# AJH_as3340_20.net
KiCad netlist of a schematic drawn in EAGLE
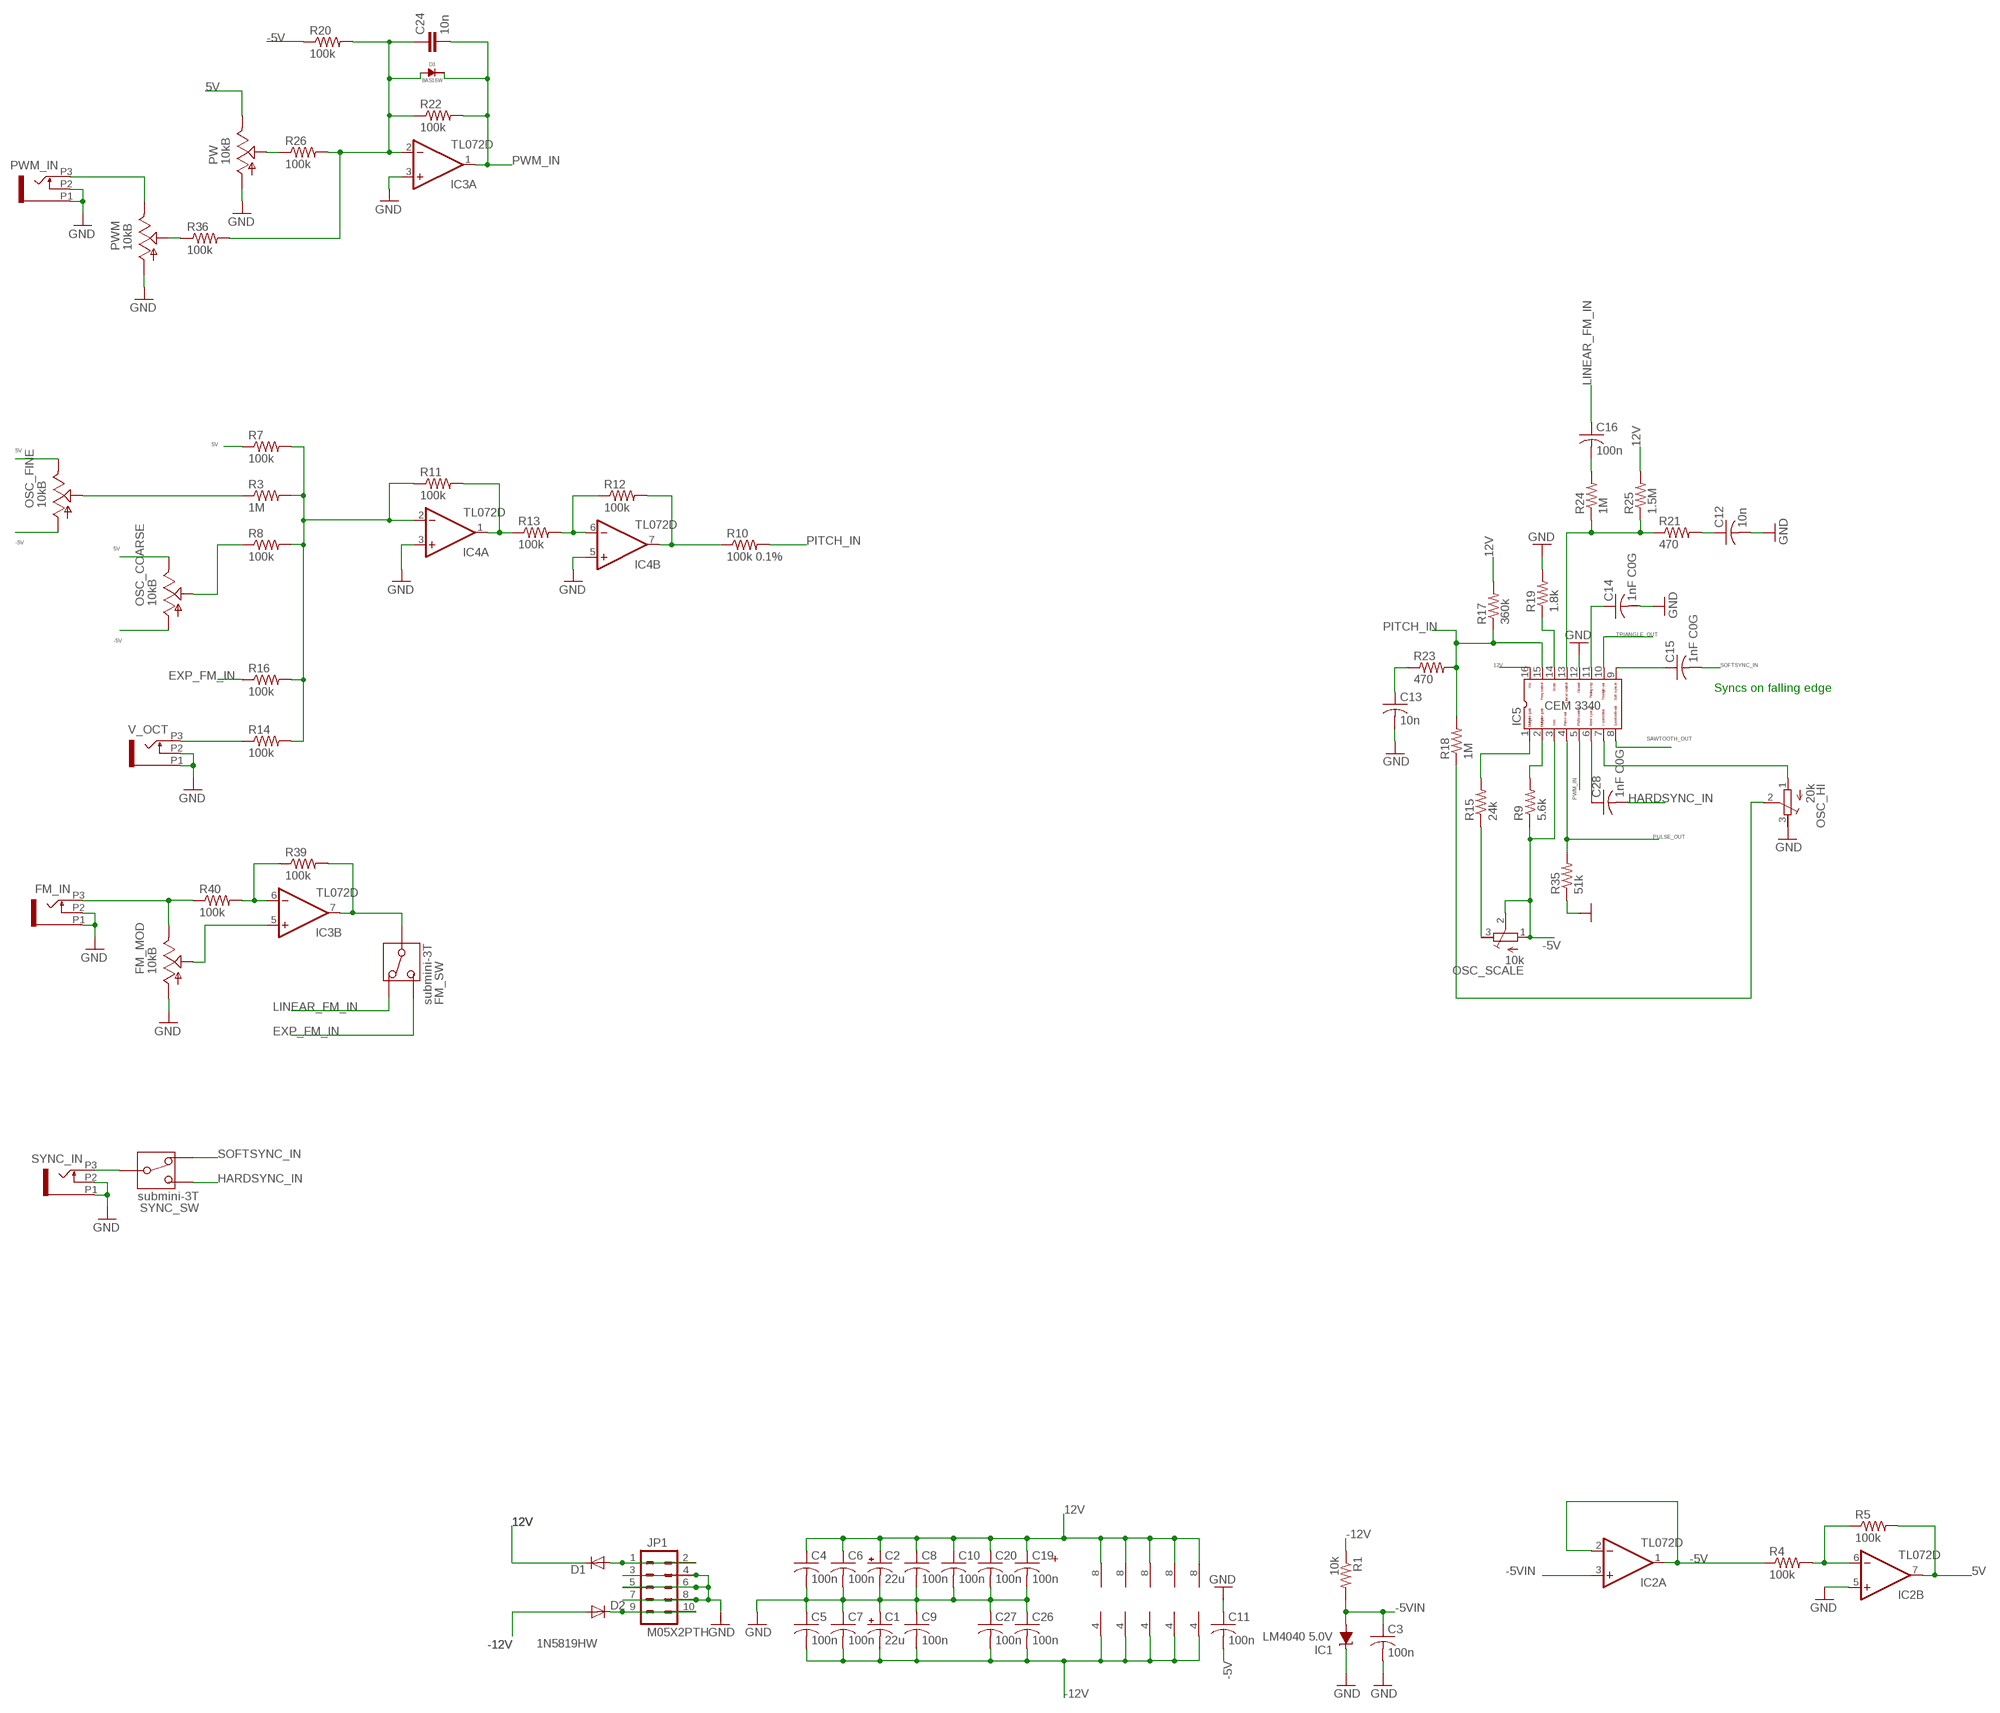
[diagram p0: schematic, sheet 1, part 1 of 2]
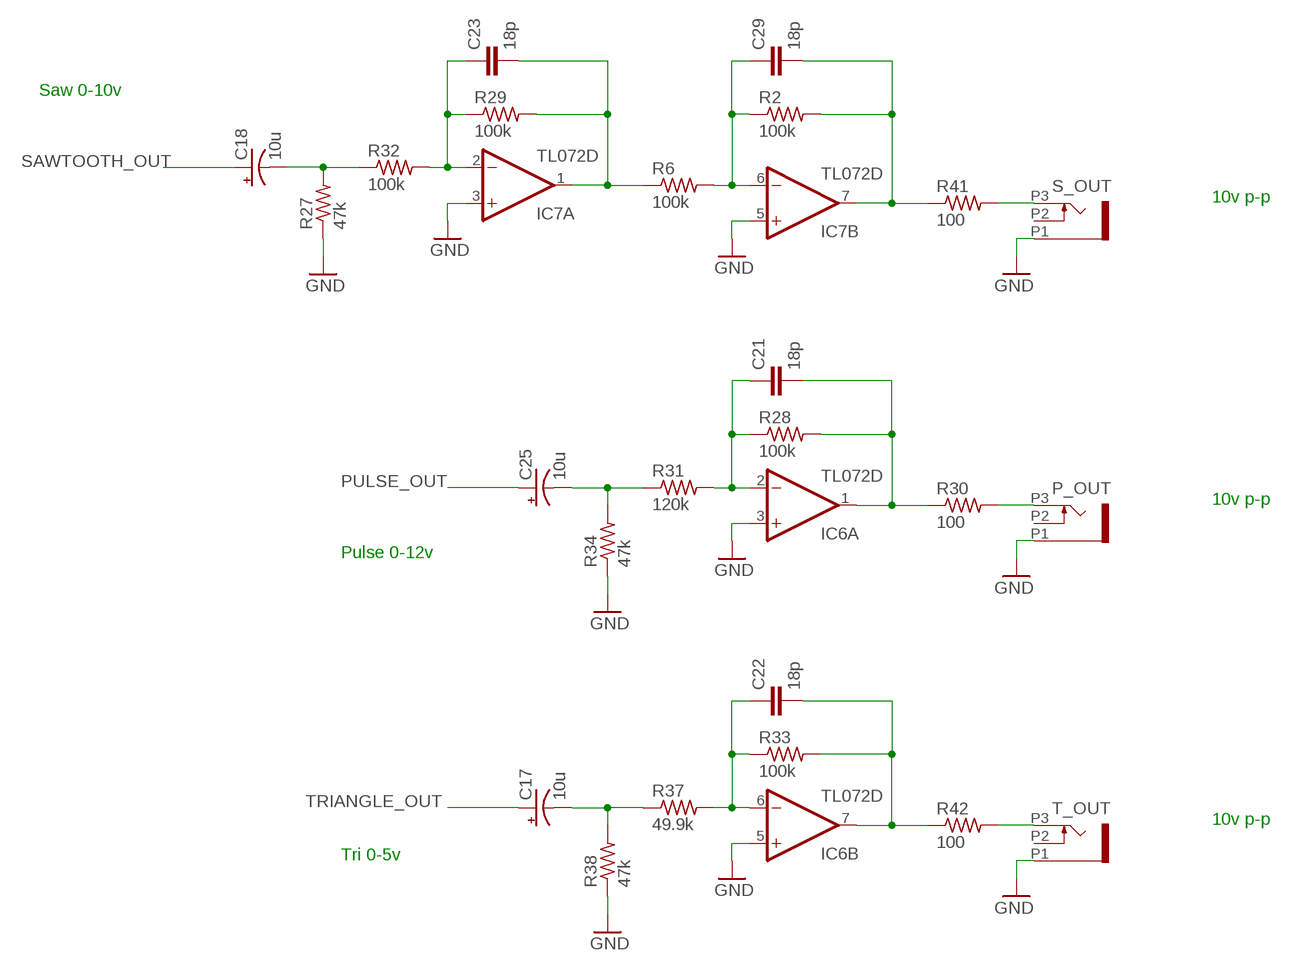
[diagram p1: schematic, sheet 1, part 2 of 2]

(export (version "E")
  (design (tool "Eeschema 10.0.6"))
  (components
    (comp (ref "C1")
      (value "22u")
      (footprint "eagle-import:PANASONIC_B")
      (libsource (lib "eagle-import") (part "CPOL-USB"))
    )
    (comp (ref "C2")
      (value "22u")
      (footprint "eagle-import:PANASONIC_B")
      (libsource (lib "eagle-import") (part "CPOL-USB"))
    )
    (comp (ref "C3")
      (value "100n")
      (footprint "eagle-import:C0603")
      (libsource (lib "eagle-import") (part "C-USC0603"))
    )
    (comp (ref "C4")
      (value "100n")
      (footprint "eagle-import:C0603")
      (libsource (lib "eagle-import") (part "C-USC0603"))
    )
    (comp (ref "C5")
      (value "100n")
      (footprint "eagle-import:C0603")
      (libsource (lib "eagle-import") (part "C-USC0603"))
    )
    (comp (ref "C6")
      (value "100n")
      (footprint "eagle-import:C0603")
      (libsource (lib "eagle-import") (part "C-USC0603"))
    )
    (comp (ref "C7")
      (value "100n")
      (footprint "eagle-import:C0603")
      (libsource (lib "eagle-import") (part "C-USC0603"))
    )
    (comp (ref "C8")
      (value "100n")
      (footprint "eagle-import:C0603")
      (libsource (lib "eagle-import") (part "C-USC0603"))
    )
    (comp (ref "C9")
      (value "100n")
      (footprint "eagle-import:C0603")
      (libsource (lib "eagle-import") (part "C-USC0603"))
    )
    (comp (ref "C10")
      (value "100n")
      (footprint "eagle-import:C0603")
      (libsource (lib "eagle-import") (part "C-USC0603"))
    )
    (comp (ref "C11")
      (value "100n")
      (footprint "eagle-import:C0603")
      (libsource (lib "eagle-import") (part "C-USC0603"))
    )
    (comp (ref "C12")
      (value "10n")
      (footprint "eagle-import:C0603")
      (libsource (lib "eagle-import") (part "C-USC0603"))
    )
    (comp (ref "C13")
      (value "10n")
      (footprint "eagle-import:C0603")
      (libsource (lib "eagle-import") (part "C-USC0603"))
    )
    (comp (ref "C14")
      (value "1nF C0G")
      (footprint "eagle-import:C0603")
      (libsource (lib "eagle-import") (part "C-USC0603"))
    )
    (comp (ref "C15")
      (value "1nF C0G")
      (footprint "eagle-import:C0603")
      (libsource (lib "eagle-import") (part "C-USC0603"))
    )
    (comp (ref "C16")
      (value "100n")
      (footprint "eagle-import:C0603")
      (libsource (lib "eagle-import") (part "C-USC0603"))
    )
    (comp (ref "C17")
      (value "10u")
      (footprint "eagle-import:PANASONIC_B")
      (libsource (lib "eagle-import") (part "CPOL-USB"))
    )
    (comp (ref "C18")
      (value "10u")
      (footprint "eagle-import:PANASONIC_B")
      (libsource (lib "eagle-import") (part "CPOL-USB"))
    )
    (comp (ref "C19")
      (value "100n")
      (footprint "eagle-import:C0603")
      (libsource (lib "eagle-import") (part "C-USC0603"))
    )
    (comp (ref "C20")
      (value "100n")
      (footprint "eagle-import:C0603")
      (libsource (lib "eagle-import") (part "C-USC0603"))
    )
    (comp (ref "C21")
      (value "18p")
      (footprint "eagle-import:C0603")
      (libsource (lib "eagle-import") (part "C-EUC0603"))
    )
    (comp (ref "C22")
      (value "18p")
      (footprint "eagle-import:C0603")
      (libsource (lib "eagle-import") (part "C-EUC0603"))
    )
    (comp (ref "C23")
      (value "18p")
      (footprint "eagle-import:C0603")
      (libsource (lib "eagle-import") (part "C-EUC0603"))
    )
    (comp (ref "C24")
      (value "10n")
      (footprint "eagle-import:C0603")
      (libsource (lib "eagle-import") (part "C-EUC0603"))
    )
    (comp (ref "C25")
      (value "10u")
      (footprint "eagle-import:PANASONIC_B")
      (libsource (lib "eagle-import") (part "CPOL-USB"))
    )
    (comp (ref "C26")
      (value "100n")
      (footprint "eagle-import:C0603")
      (libsource (lib "eagle-import") (part "C-USC0603"))
    )
    (comp (ref "C27")
      (value "100n")
      (footprint "eagle-import:C0603")
      (libsource (lib "eagle-import") (part "C-USC0603"))
    )
    (comp (ref "C28")
      (value "1nF C0G")
      (footprint "eagle-import:C0603")
      (libsource (lib "eagle-import") (part "C-USC0603"))
    )
    (comp (ref "C29")
      (value "18p")
      (footprint "eagle-import:C0603")
      (libsource (lib "eagle-import") (part "C-EUC0603"))
    )
    (comp (ref "D1")
      (value "1N5819HW")
      (footprint "eagle-import:SOD123")
      (libsource (lib "eagle-import") (part "DIODE-SOD123"))
    )
    (comp (ref "D2")
      (value "1N5819HW")
      (footprint "eagle-import:SOD123")
      (libsource (lib "eagle-import") (part "DIODE-SOD123"))
    )
    (comp (ref "D3")
      (value "BAS16W")
      (footprint "eagle-import:SOT-323")
      (libsource (lib "eagle-import") (part "BAS16W"))
    )
    (comp (ref "FM_IN")
      (value "PJ301_THONKICONN6")
      (footprint "eagle-import:WQP_PJ_301M6")
      (libsource (lib "eagle-import") (part "PJ301_THONKICONN6"))
    )
    (comp (ref "FM_MOD")
      (value "10kB")
      (footprint "eagle-import:ALPS_POT_VERTICAL_PS")
      (libsource (lib "eagle-import") (part "pot-alps_POT_USVERTICAL_PS"))
    )
    (comp (ref "FM_SW")
      (value "submini-3T")
      (footprint "eagle-import:SPDT-SUB")
      (libsource (lib "eagle-import") (part "SPDTT"))
    )
    (comp (ref "IC1")
      (value "LM4040 5.0V")
      (footprint "eagle-import:DBZ_R-PDSO-G3")
      (libsource (lib "eagle-import") (part "LM4041DBZC12"))
    )
    (comp (ref "IC2")
      (value "TL072D")
      (footprint "eagle-import:SO08")
      (libsource (lib "eagle-import") (part "TL072D"))
    )
    (comp (ref "IC3")
      (value "TL072D")
      (footprint "eagle-import:SO08")
      (libsource (lib "eagle-import") (part "TL072D"))
    )
    (comp (ref "IC4")
      (value "TL072D")
      (footprint "eagle-import:SO08")
      (libsource (lib "eagle-import") (part "TL072D"))
    )
    (comp (ref "IC5")
      (value "CEM3340SOIC16")
      (footprint "eagle-import:SO16")
      (libsource (lib "eagle-import") (part "CEM3340SOIC16"))
    )
    (comp (ref "IC6")
      (value "TL072D")
      (footprint "eagle-import:SO08")
      (libsource (lib "eagle-import") (part "TL072D"))
    )
    (comp (ref "IC7")
      (value "TL072D")
      (footprint "eagle-import:SO08")
      (libsource (lib "eagle-import") (part "TL072D"))
    )
    (comp (ref "JP1")
      (value "M05X2PTH")
      (footprint "eagle-import:AVR_ICSP")
      (libsource (lib "eagle-import") (part "M05X2PTH"))
    )
    (comp (ref "OSC_COARSE")
      (value "10kB")
      (footprint "eagle-import:ALPS_POT_VERTICAL")
      (libsource (lib "eagle-import") (part "POT_USVERTICAL"))
    )
    (comp (ref "OSC_FINE")
      (value "10kB")
      (footprint "eagle-import:ALPS_POT_VERTICAL")
      (libsource (lib "eagle-import") (part "POT_USVERTICAL"))
    )
    (comp (ref "OSC_HI")
      (value "20k")
      (footprint "eagle-import:RTRIM3296X")
      (libsource (lib "eagle-import") (part "R-TRIMM3296X"))
    )
    (comp (ref "OSC_SCALE")
      (value "10k")
      (footprint "eagle-import:RTRIM3296X")
      (libsource (lib "eagle-import") (part "R-TRIMM3296X"))
    )
    (comp (ref "PW")
      (value "10kB")
      (footprint "eagle-import:ALPS_POT_VERTICAL_PS")
      (libsource (lib "eagle-import") (part "pot-alps_POT_USVERTICAL_PS"))
    )
    (comp (ref "PWM")
      (value "10kB")
      (footprint "eagle-import:ALPS_POT_VERTICAL_PS")
      (libsource (lib "eagle-import") (part "pot-alps_POT_USVERTICAL_PS"))
    )
    (comp (ref "PWM_IN")
      (value "PJ301_THONKICONN6")
      (footprint "eagle-import:WQP_PJ_301M6")
      (libsource (lib "eagle-import") (part "PJ301_THONKICONN6"))
    )
    (comp (ref "P_OUT")
      (value "PJ301_THONKICONN6")
      (footprint "eagle-import:WQP_PJ_301M6")
      (libsource (lib "eagle-import") (part "PJ301_THONKICONN6"))
    )
    (comp (ref "R1")
      (value "10k")
      (footprint "eagle-import:R0603")
      (libsource (lib "eagle-import") (part "R-US_R0603"))
    )
    (comp (ref "R2")
      (value "100k")
      (footprint "eagle-import:R0603")
      (libsource (lib "eagle-import") (part "R-US_R0603"))
    )
    (comp (ref "R3")
      (value "1M")
      (footprint "eagle-import:R0603")
      (libsource (lib "eagle-import") (part "R-US_R0603"))
    )
    (comp (ref "R4")
      (value "100k")
      (footprint "eagle-import:R0603")
      (libsource (lib "eagle-import") (part "R-US_R0603"))
    )
    (comp (ref "R5")
      (value "100k")
      (footprint "eagle-import:R0603")
      (libsource (lib "eagle-import") (part "R-US_R0603"))
    )
    (comp (ref "R6")
      (value "100k")
      (footprint "eagle-import:R0603")
      (libsource (lib "eagle-import") (part "R-US_R0603"))
    )
    (comp (ref "R7")
      (value "100k")
      (footprint "eagle-import:R0603")
      (libsource (lib "eagle-import") (part "R-US_R0603"))
    )
    (comp (ref "R8")
      (value "100k")
      (footprint "eagle-import:R0603")
      (libsource (lib "eagle-import") (part "R-US_R0603"))
    )
    (comp (ref "R9")
      (value "5.6k")
      (footprint "eagle-import:R0603")
      (libsource (lib "eagle-import") (part "R-US_R0603"))
    )
    (comp (ref "R10")
      (value "100k 0.1%")
      (footprint "eagle-import:R0603")
      (libsource (lib "eagle-import") (part "R-US_R0603"))
    )
    (comp (ref "R11")
      (value "100k")
      (footprint "eagle-import:R0603")
      (libsource (lib "eagle-import") (part "R-US_R0603"))
    )
    (comp (ref "R12")
      (value "100k")
      (footprint "eagle-import:R0603")
      (libsource (lib "eagle-import") (part "R-US_R0603"))
    )
    (comp (ref "R13")
      (value "100k")
      (footprint "eagle-import:R0603")
      (libsource (lib "eagle-import") (part "R-US_R0603"))
    )
    (comp (ref "R14")
      (value "100k")
      (footprint "eagle-import:R0603")
      (libsource (lib "eagle-import") (part "R-US_R0603"))
    )
    (comp (ref "R15")
      (value "24k")
      (footprint "eagle-import:R0603")
      (libsource (lib "eagle-import") (part "R-US_R0603"))
    )
    (comp (ref "R16")
      (value "100k")
      (footprint "eagle-import:R0603")
      (libsource (lib "eagle-import") (part "R-US_R0603"))
    )
    (comp (ref "R17")
      (value "360k")
      (footprint "eagle-import:R0603")
      (libsource (lib "eagle-import") (part "R-US_R0603"))
    )
    (comp (ref "R18")
      (value "1M")
      (footprint "eagle-import:R0603")
      (libsource (lib "eagle-import") (part "R-US_R0603"))
    )
    (comp (ref "R19")
      (value "1.8k")
      (footprint "eagle-import:R0603")
      (libsource (lib "eagle-import") (part "R-US_R0603"))
    )
    (comp (ref "R20")
      (value "100k")
      (footprint "eagle-import:R0603")
      (libsource (lib "eagle-import") (part "R-US_R0603"))
    )
    (comp (ref "R21")
      (value "470")
      (footprint "eagle-import:R0603")
      (libsource (lib "eagle-import") (part "R-US_R0603"))
    )
    (comp (ref "R22")
      (value "100k")
      (footprint "eagle-import:R0603")
      (libsource (lib "eagle-import") (part "R-US_R0603"))
    )
    (comp (ref "R23")
      (value "470")
      (footprint "eagle-import:R0603")
      (libsource (lib "eagle-import") (part "R-US_R0603"))
    )
    (comp (ref "R24")
      (value "1M")
      (footprint "eagle-import:R0603")
      (libsource (lib "eagle-import") (part "R-US_R0603"))
    )
    (comp (ref "R25")
      (value "1.5M")
      (footprint "eagle-import:R0603")
      (libsource (lib "eagle-import") (part "R-US_R0603"))
    )
    (comp (ref "R26")
      (value "100k")
      (footprint "eagle-import:R0603")
      (libsource (lib "eagle-import") (part "R-US_R0603"))
    )
    (comp (ref "R27")
      (value "47k")
      (footprint "eagle-import:R0603")
      (libsource (lib "eagle-import") (part "R-US_R0603"))
    )
    (comp (ref "R28")
      (value "100k")
      (footprint "eagle-import:R0603")
      (libsource (lib "eagle-import") (part "R-US_R0603"))
    )
    (comp (ref "R29")
      (value "100k")
      (footprint "eagle-import:R0603")
      (libsource (lib "eagle-import") (part "R-US_R0603"))
    )
    (comp (ref "R30")
      (value "100")
      (footprint "eagle-import:R0603")
      (libsource (lib "eagle-import") (part "R-US_R0603"))
    )
    (comp (ref "R31")
      (value "120k")
      (footprint "eagle-import:R0603")
      (libsource (lib "eagle-import") (part "R-US_R0603"))
    )
    (comp (ref "R32")
      (value "100k")
      (footprint "eagle-import:R0603")
      (libsource (lib "eagle-import") (part "R-US_R0603"))
    )
    (comp (ref "R33")
      (value "100k")
      (footprint "eagle-import:R0603")
      (libsource (lib "eagle-import") (part "R-US_R0603"))
    )
    (comp (ref "R34")
      (value "47k")
      (footprint "eagle-import:R0603")
      (libsource (lib "eagle-import") (part "R-US_R0603"))
    )
    (comp (ref "R35")
      (value "51k")
      (footprint "eagle-import:R0603")
      (libsource (lib "eagle-import") (part "R-US_R0603"))
    )
    (comp (ref "R36")
      (value "100k")
      (footprint "eagle-import:R0603")
      (libsource (lib "eagle-import") (part "R-US_R0603"))
    )
    (comp (ref "R37")
      (value "49.9k")
      (footprint "eagle-import:R0603")
      (libsource (lib "eagle-import") (part "R-US_R0603"))
    )
    (comp (ref "R38")
      (value "47k")
      (footprint "eagle-import:R0603")
      (libsource (lib "eagle-import") (part "R-US_R0603"))
    )
    (comp (ref "R39")
      (value "100k")
      (footprint "eagle-import:R0603")
      (libsource (lib "eagle-import") (part "R-US_R0603"))
    )
    (comp (ref "R40")
      (value "100k")
      (footprint "eagle-import:R0603")
      (libsource (lib "eagle-import") (part "R-US_R0603"))
    )
    (comp (ref "R41")
      (value "100")
      (footprint "eagle-import:R0603")
      (libsource (lib "eagle-import") (part "R-US_R0603"))
    )
    (comp (ref "R42")
      (value "100")
      (footprint "eagle-import:R0603")
      (libsource (lib "eagle-import") (part "R-US_R0603"))
    )
    (comp (ref "SYNC_IN")
      (value "PJ301_THONKICONN6")
      (footprint "eagle-import:WQP_PJ_301M6")
      (libsource (lib "eagle-import") (part "PJ301_THONKICONN6"))
    )
    (comp (ref "SYNC_SW")
      (value "submini-3T")
      (footprint "eagle-import:SPDT-SUB")
      (libsource (lib "eagle-import") (part "SPDTT"))
    )
    (comp (ref "S_OUT")
      (value "PJ301_THONKICONN6")
      (footprint "eagle-import:WQP_PJ_301M6")
      (libsource (lib "eagle-import") (part "PJ301_THONKICONN6"))
    )
    (comp (ref "T_OUT")
      (value "PJ301_THONKICONN6")
      (footprint "eagle-import:WQP_PJ_301M6")
      (libsource (lib "eagle-import") (part "PJ301_THONKICONN6"))
    )
    (comp (ref "V_OCT")
      (value "PJ301_THONKICONN6")
      (footprint "eagle-import:WQP_PJ_301M6")
      (libsource (lib "eagle-import") (part "PJ301_THONKICONN6"))
    )
  )
  (nets
    (net (code "1") (name "/-5V") (class "Default")
      (node (ref "C11") (pin "2") (pinfunction "2_2") (pintype "passive"))
      (node (ref "IC2") (pin "1") (pinfunction "OUT_1") (pintype "output"))
      (node (ref "IC2") (pin "2") (pinfunction "-IN_2") (pintype "input"))
      (node (ref "IC5") (pin "3") (pinfunction "3_3") (pintype "power_in"))
      (node (ref "OSC_COARSE") (pin "P$3") (pinfunction "A_P$3") (pintype "passive"))
      (node (ref "OSC_FINE") (pin "P$3") (pinfunction "A_P$3") (pintype "passive"))
      (node (ref "OSC_SCALE") (pin "1") (pinfunction "E_1") (pintype "passive"))
      (node (ref "OSC_SCALE") (pin "2") (pinfunction "S_2") (pintype "passive"))
      (node (ref "R20") (pin "1") (pinfunction "1_1") (pintype "passive"))
      (node (ref "R4") (pin "1") (pinfunction "1_1") (pintype "passive"))
      (node (ref "R9") (pin "1") (pinfunction "1_1") (pintype "passive"))
    )
    (net (code "2") (name "/-5VIN") (class "Default")
      (node (ref "C3") (pin "1") (pinfunction "1_1") (pintype "passive"))
      (node (ref "IC1") (pin "2") (pinfunction "A_2") (pintype "passive"))
      (node (ref "IC2") (pin "3") (pinfunction "+IN_3") (pintype "input"))
      (node (ref "R1") (pin "2") (pinfunction "2_2") (pintype "passive"))
    )
    (net (code "3") (name "/-12V") (class "Default")
      (node (ref "C1") (pin "-") (pinfunction "-_-") (pintype "passive"))
      (node (ref "C26") (pin "2") (pinfunction "2_2") (pintype "passive"))
      (node (ref "C27") (pin "2") (pinfunction "2_2") (pintype "passive"))
      (node (ref "C5") (pin "2") (pinfunction "2_2") (pintype "passive"))
      (node (ref "C7") (pin "2") (pinfunction "2_2") (pintype "passive"))
      (node (ref "C9") (pin "2") (pinfunction "2_2") (pintype "passive"))
      (node (ref "D2") (pin "A") (pinfunction "A_A") (pintype "passive"))
      (node (ref "IC2") (pin "4") (pinfunction "V-_4") (pintype "power_in"))
      (node (ref "IC3") (pin "4") (pinfunction "V-_4") (pintype "power_in"))
      (node (ref "IC4") (pin "4") (pinfunction "V-_4") (pintype "power_in"))
      (node (ref "IC6") (pin "4") (pinfunction "V-_4") (pintype "power_in"))
      (node (ref "IC7") (pin "4") (pinfunction "V-_4") (pintype "power_in"))
      (node (ref "R1") (pin "1") (pinfunction "1_1") (pintype "passive"))
    )
    (net (code "4") (name "/5V") (class "Default")
      (node (ref "IC2") (pin "7") (pinfunction "OUT_7") (pintype "output"))
      (node (ref "OSC_COARSE") (pin "P$1") (pinfunction "E_P$1") (pintype "passive"))
      (node (ref "OSC_FINE") (pin "P$1") (pinfunction "E_P$1") (pintype "passive"))
      (node (ref "PW") (pin "P$1") (pinfunction "E_P$1") (pintype "passive"))
      (node (ref "R5") (pin "2") (pinfunction "2_2") (pintype "passive"))
      (node (ref "R7") (pin "1") (pinfunction "1_1") (pintype "passive"))
    )
    (net (code "5") (name "/12V") (class "Default")
      (node (ref "C10") (pin "1") (pinfunction "1_1") (pintype "passive"))
      (node (ref "C19") (pin "1") (pinfunction "1_1") (pintype "passive"))
      (node (ref "C2") (pin "+") (pinfunction "+_+") (pintype "passive"))
      (node (ref "C20") (pin "1") (pinfunction "1_1") (pintype "passive"))
      (node (ref "C4") (pin "1") (pinfunction "1_1") (pintype "passive"))
      (node (ref "C6") (pin "1") (pinfunction "1_1") (pintype "passive"))
      (node (ref "C8") (pin "1") (pinfunction "1_1") (pintype "passive"))
      (node (ref "D1") (pin "C") (pinfunction "C_C") (pintype "passive"))
      (node (ref "IC2") (pin "8") (pinfunction "V+_8") (pintype "power_in"))
      (node (ref "IC3") (pin "8") (pinfunction "V+_8") (pintype "power_in"))
      (node (ref "IC4") (pin "8") (pinfunction "V+_8") (pintype "power_in"))
      (node (ref "IC5") (pin "16") (pinfunction "16_16") (pintype "power_in"))
      (node (ref "IC6") (pin "8") (pinfunction "V+_8") (pintype "power_in"))
      (node (ref "IC7") (pin "8") (pinfunction "V+_8") (pintype "power_in"))
      (node (ref "R17") (pin "2") (pinfunction "2_2") (pintype "passive"))
      (node (ref "R25") (pin "2") (pinfunction "2_2") (pintype "passive"))
    )
    (net (code "6") (name "/EXP_FM_IN") (class "Default")
      (node (ref "FM_SW") (pin "P$1") (pinfunction "P$1_P$1") (pintype "passive"))
      (node (ref "R16") (pin "1") (pinfunction "1_1") (pintype "passive"))
    )
    (net (code "7") (name "/HARDSYNC_IN") (class "Default")
      (node (ref "C28") (pin "2") (pinfunction "2_2") (pintype "passive"))
      (node (ref "SYNC_SW") (pin "P$1") (pinfunction "P$1_P$1") (pintype "passive"))
    )
    (net (code "8") (name "/LINEAR_FM_IN") (class "Default")
      (node (ref "C16") (pin "1") (pinfunction "1_1") (pintype "passive"))
      (node (ref "FM_SW") (pin "P$3") (pinfunction "P$3_P$3") (pintype "passive"))
    )
    (net (code "9") (name "/PITCH_IN") (class "Default")
      (node (ref "IC5") (pin "15") (pinfunction "15_15") (pintype "input"))
      (node (ref "R10") (pin "2") (pinfunction "2_2") (pintype "passive"))
      (node (ref "R17") (pin "1") (pinfunction "1_1") (pintype "passive"))
      (node (ref "R18") (pin "2") (pinfunction "2_2") (pintype "passive"))
      (node (ref "R23") (pin "2") (pinfunction "2_2") (pintype "passive"))
    )
    (net (code "10") (name "/PULSE_OUT") (class "Default")
      (node (ref "C25") (pin "+") (pinfunction "+_+") (pintype "passive"))
      (node (ref "IC5") (pin "4") (pinfunction "4_4") (pintype "output"))
      (node (ref "R35") (pin "2") (pinfunction "2_2") (pintype "passive"))
    )
    (net (code "11") (name "/PWM_IN") (class "Default")
      (node (ref "C24") (pin "2") (pinfunction "2_2") (pintype "passive"))
      (node (ref "D3") (pin "CATHODE") (pinfunction "CATHODE_CATHODE") (pintype "bidirectional"))
      (node (ref "IC3") (pin "1") (pinfunction "OUT_1") (pintype "output"))
      (node (ref "IC5") (pin "5") (pinfunction "5_5") (pintype "input"))
      (node (ref "R22") (pin "2") (pinfunction "2_2") (pintype "passive"))
    )
    (net (code "12") (name "/SAWTOOTH_OUT") (class "Default")
      (node (ref "C18") (pin "+") (pinfunction "+_+") (pintype "passive"))
      (node (ref "IC5") (pin "8") (pinfunction "8_8") (pintype "output"))
    )
    (net (code "13") (name "/SOFTSYNC_IN") (class "Default")
      (node (ref "C15") (pin "2") (pinfunction "2_2") (pintype "passive"))
      (node (ref "SYNC_SW") (pin "P$3") (pinfunction "P$3_P$3") (pintype "passive"))
    )
    (net (code "14") (name "/TRIANGLE_OUT") (class "Default")
      (node (ref "C17") (pin "+") (pinfunction "+_+") (pintype "passive"))
      (node (ref "IC5") (pin "10") (pinfunction "10_10") (pintype "output"))
    )
    (net (code "15") (name "GND") (class "Default")
      (node (ref "C1") (pin "+") (pinfunction "+_+") (pintype "passive"))
      (node (ref "C10") (pin "2") (pinfunction "2_2") (pintype "passive"))
      (node (ref "C11") (pin "1") (pinfunction "1_1") (pintype "passive"))
      (node (ref "C12") (pin "2") (pinfunction "2_2") (pintype "passive"))
      (node (ref "C13") (pin "2") (pinfunction "2_2") (pintype "passive"))
      (node (ref "C14") (pin "2") (pinfunction "2_2") (pintype "passive"))
      (node (ref "C19") (pin "2") (pinfunction "2_2") (pintype "passive"))
      (node (ref "C2") (pin "-") (pinfunction "-_-") (pintype "passive"))
      (node (ref "C20") (pin "2") (pinfunction "2_2") (pintype "passive"))
      (node (ref "C26") (pin "1") (pinfunction "1_1") (pintype "passive"))
      (node (ref "C27") (pin "1") (pinfunction "1_1") (pintype "passive"))
      (node (ref "C3") (pin "2") (pinfunction "2_2") (pintype "passive"))
      (node (ref "C4") (pin "2") (pinfunction "2_2") (pintype "passive"))
      (node (ref "C5") (pin "1") (pinfunction "1_1") (pintype "passive"))
      (node (ref "C6") (pin "2") (pinfunction "2_2") (pintype "passive"))
      (node (ref "C7") (pin "1") (pinfunction "1_1") (pintype "passive"))
      (node (ref "C8") (pin "2") (pinfunction "2_2") (pintype "passive"))
      (node (ref "C9") (pin "1") (pinfunction "1_1") (pintype "passive"))
      (node (ref "FM_IN") (pin "P1") (pinfunction "1_P1") (pintype "passive"))
      (node (ref "FM_IN") (pin "P2") (pinfunction "2_P2") (pintype "passive"))
      (node (ref "FM_MOD") (pin "P$3") (pinfunction "A_P$3") (pintype "passive"))
      (node (ref "IC1") (pin "1") (pinfunction "C_1") (pintype "passive"))
      (node (ref "IC2") (pin "5") (pinfunction "+IN_5") (pintype "input"))
      (node (ref "IC3") (pin "3") (pinfunction "+IN_3") (pintype "input"))
      (node (ref "IC4") (pin "3") (pinfunction "+IN_3") (pintype "input"))
      (node (ref "IC4") (pin "5") (pinfunction "+IN_5") (pintype "input"))
      (node (ref "IC5") (pin "12") (pinfunction "12_12") (pintype "power_in"))
      (node (ref "IC6") (pin "3") (pinfunction "+IN_3") (pintype "input"))
      (node (ref "IC6") (pin "5") (pinfunction "+IN_5") (pintype "input"))
      (node (ref "IC7") (pin "3") (pinfunction "+IN_3") (pintype "input"))
      (node (ref "IC7") (pin "5") (pinfunction "+IN_5") (pintype "input"))
      (node (ref "JP1") (pin "3") (pinfunction "3_3") (pintype "passive"))
      (node (ref "JP1") (pin "4") (pinfunction "4_4") (pintype "passive"))
      (node (ref "JP1") (pin "5") (pinfunction "5_5") (pintype "passive"))
      (node (ref "JP1") (pin "6") (pinfunction "6_6") (pintype "passive"))
      (node (ref "JP1") (pin "7") (pinfunction "7_7") (pintype "passive"))
      (node (ref "JP1") (pin "8") (pinfunction "8_8") (pintype "passive"))
      (node (ref "OSC_HI") (pin "3") (pinfunction "A_3") (pintype "passive"))
      (node (ref "PW") (pin "P$3") (pinfunction "A_P$3") (pintype "passive"))
      (node (ref "PWM") (pin "P$3") (pinfunction "A_P$3") (pintype "passive"))
      (node (ref "PWM_IN") (pin "P1") (pinfunction "1_P1") (pintype "passive"))
      (node (ref "PWM_IN") (pin "P2") (pinfunction "2_P2") (pintype "passive"))
      (node (ref "P_OUT") (pin "P1") (pinfunction "1_P1") (pintype "passive"))
      (node (ref "R19") (pin "2") (pinfunction "2_2") (pintype "passive"))
      (node (ref "R27") (pin "1") (pinfunction "1_1") (pintype "passive"))
      (node (ref "R34") (pin "1") (pinfunction "1_1") (pintype "passive"))
      (node (ref "R35") (pin "1") (pinfunction "1_1") (pintype "passive"))
      (node (ref "R38") (pin "1") (pinfunction "1_1") (pintype "passive"))
      (node (ref "SYNC_IN") (pin "P1") (pinfunction "1_P1") (pintype "passive"))
      (node (ref "SYNC_IN") (pin "P2") (pinfunction "2_P2") (pintype "passive"))
      (node (ref "S_OUT") (pin "P1") (pinfunction "1_P1") (pintype "passive"))
      (node (ref "T_OUT") (pin "P1") (pinfunction "1_P1") (pintype "passive"))
      (node (ref "V_OCT") (pin "P1") (pinfunction "1_P1") (pintype "passive"))
      (node (ref "V_OCT") (pin "P2") (pinfunction "2_P2") (pintype "passive"))
    )
    (net (code "16") (name "Net-(C12-Pad1)") (class "Default")
      (node (ref "C12") (pin "1") (pinfunction "1_1") (pintype "passive"))
      (node (ref "R21") (pin "2") (pinfunction "2_2") (pintype "passive"))
    )
    (net (code "17") (name "Net-(C13-Pad1)") (class "Default")
      (node (ref "C13") (pin "1") (pinfunction "1_1") (pintype "passive"))
      (node (ref "R23") (pin "1") (pinfunction "1_1") (pintype "passive"))
    )
    (net (code "18") (name "Net-(C14-Pad1)") (class "Default")
      (node (ref "C14") (pin "1") (pinfunction "1_1") (pintype "passive"))
      (node (ref "IC5") (pin "11") (pinfunction "11_11") (pintype "bidirectional"))
    )
    (net (code "19") (name "Net-(C15-Pad1)") (class "Default")
      (node (ref "C15") (pin "1") (pinfunction "1_1") (pintype "passive"))
      (node (ref "IC5") (pin "9") (pinfunction "9_9") (pintype "input"))
    )
    (net (code "20") (name "Net-(C16-Pad2)") (class "Default")
      (node (ref "C16") (pin "2") (pinfunction "2_2") (pintype "passive"))
      (node (ref "R24") (pin "2") (pinfunction "2_2") (pintype "passive"))
    )
    (net (code "21") (name "Net-(C17-Pad-)") (class "Default")
      (node (ref "C17") (pin "-") (pinfunction "-_-") (pintype "passive"))
      (node (ref "R37") (pin "1") (pinfunction "1_1") (pintype "passive"))
      (node (ref "R38") (pin "2") (pinfunction "2_2") (pintype "passive"))
    )
    (net (code "22") (name "Net-(C18-Pad-)") (class "Default")
      (node (ref "C18") (pin "-") (pinfunction "-_-") (pintype "passive"))
      (node (ref "R27") (pin "2") (pinfunction "2_2") (pintype "passive"))
      (node (ref "R32") (pin "1") (pinfunction "1_1") (pintype "passive"))
    )
    (net (code "23") (name "Net-(C25-Pad-)") (class "Default")
      (node (ref "C25") (pin "-") (pinfunction "-_-") (pintype "passive"))
      (node (ref "R31") (pin "1") (pinfunction "1_1") (pintype "passive"))
      (node (ref "R34") (pin "2") (pinfunction "2_2") (pintype "passive"))
    )
    (net (code "24") (name "Net-(C28-Pad1)") (class "Default")
      (node (ref "C28") (pin "1") (pinfunction "1_1") (pintype "passive"))
      (node (ref "IC5") (pin "6") (pinfunction "6_6") (pintype "input"))
    )
    (net (code "25") (name "Net-(D1-PadA)") (class "Default")
      (node (ref "D1") (pin "A") (pinfunction "A_A") (pintype "passive"))
      (node (ref "JP1") (pin "1") (pinfunction "1_1") (pintype "passive"))
      (node (ref "JP1") (pin "2") (pinfunction "2_2") (pintype "passive"))
    )
    (net (code "26") (name "Net-(D2-PadC)") (class "Default")
      (node (ref "D2") (pin "C") (pinfunction "C_C") (pintype "passive"))
      (node (ref "JP1") (pin "10") (pinfunction "10_10") (pintype "passive"))
      (node (ref "JP1") (pin "9") (pinfunction "9_9") (pintype "passive"))
    )
    (net (code "27") (name "Net-(FM_IN-3)") (class "Default")
      (node (ref "FM_IN") (pin "P3") (pinfunction "3_P3") (pintype "passive"))
      (node (ref "FM_MOD") (pin "P$1") (pinfunction "E_P$1") (pintype "passive"))
      (node (ref "R40") (pin "1") (pinfunction "1_1") (pintype "passive"))
    )
    (net (code "28") (name "Net-(FM_MOD-S)") (class "Default")
      (node (ref "FM_MOD") (pin "P$2") (pinfunction "S_P$2") (pintype "passive"))
      (node (ref "IC3") (pin "5") (pinfunction "+IN_5") (pintype "input"))
    )
    (net (code "29") (name "Net-(IC2B--IN)") (class "Default")
      (node (ref "IC2") (pin "6") (pinfunction "-IN_6") (pintype "input"))
      (node (ref "R4") (pin "2") (pinfunction "2_2") (pintype "passive"))
      (node (ref "R5") (pin "1") (pinfunction "1_1") (pintype "passive"))
    )
    (net (code "30") (name "Net-(IC3A--IN)") (class "Default")
      (node (ref "C24") (pin "1") (pinfunction "1_1") (pintype "passive"))
      (node (ref "D3") (pin "ANODE") (pinfunction "ANODE_ANODE") (pintype "bidirectional"))
      (node (ref "IC3") (pin "2") (pinfunction "-IN_2") (pintype "input"))
      (node (ref "R20") (pin "2") (pinfunction "2_2") (pintype "passive"))
      (node (ref "R22") (pin "1") (pinfunction "1_1") (pintype "passive"))
      (node (ref "R26") (pin "2") (pinfunction "2_2") (pintype "passive"))
      (node (ref "R36") (pin "2") (pinfunction "2_2") (pintype "passive"))
    )
    (net (code "31") (name "Net-(IC3B--IN)") (class "Default")
      (node (ref "IC3") (pin "6") (pinfunction "-IN_6") (pintype "input"))
      (node (ref "R39") (pin "1") (pinfunction "1_1") (pintype "passive"))
      (node (ref "R40") (pin "2") (pinfunction "2_2") (pintype "passive"))
    )
    (net (code "32") (name "Net-(IC3B-OUT)") (class "Default")
      (node (ref "FM_SW") (pin "P$2") (pinfunction "P$2_P$2") (pintype "passive"))
      (node (ref "IC3") (pin "7") (pinfunction "OUT_7") (pintype "output"))
      (node (ref "R39") (pin "2") (pinfunction "2_2") (pintype "passive"))
    )
    (net (code "33") (name "Net-(IC4A--IN)") (class "Default")
      (node (ref "IC4") (pin "2") (pinfunction "-IN_2") (pintype "input"))
      (node (ref "R11") (pin "1") (pinfunction "1_1") (pintype "passive"))
      (node (ref "R14") (pin "2") (pinfunction "2_2") (pintype "passive"))
      (node (ref "R16") (pin "2") (pinfunction "2_2") (pintype "passive"))
      (node (ref "R3") (pin "2") (pinfunction "2_2") (pintype "passive"))
      (node (ref "R7") (pin "2") (pinfunction "2_2") (pintype "passive"))
      (node (ref "R8") (pin "2") (pinfunction "2_2") (pintype "passive"))
    )
    (net (code "34") (name "Net-(IC4A-OUT)") (class "Default")
      (node (ref "IC4") (pin "1") (pinfunction "OUT_1") (pintype "output"))
      (node (ref "R11") (pin "2") (pinfunction "2_2") (pintype "passive"))
      (node (ref "R13") (pin "1") (pinfunction "1_1") (pintype "passive"))
    )
    (net (code "35") (name "Net-(IC4B--IN)") (class "Default")
      (node (ref "IC4") (pin "6") (pinfunction "-IN_6") (pintype "input"))
      (node (ref "R12") (pin "1") (pinfunction "1_1") (pintype "passive"))
      (node (ref "R13") (pin "2") (pinfunction "2_2") (pintype "passive"))
    )
    (net (code "36") (name "Net-(IC4B-OUT)") (class "Default")
      (node (ref "IC4") (pin "7") (pinfunction "OUT_7") (pintype "output"))
      (node (ref "R10") (pin "1") (pinfunction "1_1") (pintype "passive"))
      (node (ref "R12") (pin "2") (pinfunction "2_2") (pintype "passive"))
    )
    (net (code "37") (name "Net-(IC5-Pad1)") (class "Default")
      (node (ref "IC5") (pin "1") (pinfunction "1_1") (pintype "bidirectional"))
      (node (ref "R15") (pin "2") (pinfunction "2_2") (pintype "passive"))
    )
    (net (code "38") (name "Net-(IC5-Pad2)") (class "Default")
      (node (ref "IC5") (pin "2") (pinfunction "2_2") (pintype "bidirectional"))
      (node (ref "R9") (pin "2") (pinfunction "2_2") (pintype "passive"))
    )
    (net (code "39") (name "Net-(IC5-Pad13)") (class "Default")
      (node (ref "IC5") (pin "13") (pinfunction "13_13") (pintype "input"))
      (node (ref "R21") (pin "1") (pinfunction "1_1") (pintype "passive"))
      (node (ref "R24") (pin "1") (pinfunction "1_1") (pintype "passive"))
      (node (ref "R25") (pin "1") (pinfunction "1_1") (pintype "passive"))
    )
    (net (code "40") (name "Net-(IC5-Pad14)") (class "Default")
      (node (ref "IC5") (pin "14") (pinfunction "14_14") (pintype "input"))
      (node (ref "R19") (pin "1") (pinfunction "1_1") (pintype "passive"))
    )
    (net (code "41") (name "Net-(IC6A--IN)") (class "Default")
      (node (ref "C21") (pin "1") (pinfunction "1_1") (pintype "passive"))
      (node (ref "IC6") (pin "2") (pinfunction "-IN_2") (pintype "input"))
      (node (ref "R28") (pin "1") (pinfunction "1_1") (pintype "passive"))
      (node (ref "R31") (pin "2") (pinfunction "2_2") (pintype "passive"))
    )
    (net (code "42") (name "Net-(IC6A-OUT)") (class "Default")
      (node (ref "C21") (pin "2") (pinfunction "2_2") (pintype "passive"))
      (node (ref "IC6") (pin "1") (pinfunction "OUT_1") (pintype "output"))
      (node (ref "R28") (pin "2") (pinfunction "2_2") (pintype "passive"))
      (node (ref "R30") (pin "1") (pinfunction "1_1") (pintype "passive"))
    )
    (net (code "43") (name "Net-(IC6B--IN)") (class "Default")
      (node (ref "C22") (pin "1") (pinfunction "1_1") (pintype "passive"))
      (node (ref "IC6") (pin "6") (pinfunction "-IN_6") (pintype "input"))
      (node (ref "R33") (pin "1") (pinfunction "1_1") (pintype "passive"))
      (node (ref "R37") (pin "2") (pinfunction "2_2") (pintype "passive"))
    )
    (net (code "44") (name "Net-(IC6B-OUT)") (class "Default")
      (node (ref "C22") (pin "2") (pinfunction "2_2") (pintype "passive"))
      (node (ref "IC6") (pin "7") (pinfunction "OUT_7") (pintype "output"))
      (node (ref "R33") (pin "2") (pinfunction "2_2") (pintype "passive"))
      (node (ref "R42") (pin "1") (pinfunction "1_1") (pintype "passive"))
    )
    (net (code "45") (name "Net-(IC7A--IN)") (class "Default")
      (node (ref "C23") (pin "1") (pinfunction "1_1") (pintype "passive"))
      (node (ref "IC7") (pin "2") (pinfunction "-IN_2") (pintype "input"))
      (node (ref "R29") (pin "1") (pinfunction "1_1") (pintype "passive"))
      (node (ref "R32") (pin "2") (pinfunction "2_2") (pintype "passive"))
    )
    (net (code "46") (name "Net-(IC7A-OUT)") (class "Default")
      (node (ref "C23") (pin "2") (pinfunction "2_2") (pintype "passive"))
      (node (ref "IC7") (pin "1") (pinfunction "OUT_1") (pintype "output"))
      (node (ref "R29") (pin "2") (pinfunction "2_2") (pintype "passive"))
      (node (ref "R6") (pin "1") (pinfunction "1_1") (pintype "passive"))
    )
    (net (code "47") (name "Net-(IC7B--IN)") (class "Default")
      (node (ref "C29") (pin "1") (pinfunction "1_1") (pintype "passive"))
      (node (ref "IC7") (pin "6") (pinfunction "-IN_6") (pintype "input"))
      (node (ref "R2") (pin "1") (pinfunction "1_1") (pintype "passive"))
      (node (ref "R6") (pin "2") (pinfunction "2_2") (pintype "passive"))
    )
    (net (code "48") (name "Net-(IC7B-OUT)") (class "Default")
      (node (ref "C29") (pin "2") (pinfunction "2_2") (pintype "passive"))
      (node (ref "IC7") (pin "7") (pinfunction "OUT_7") (pintype "output"))
      (node (ref "R2") (pin "2") (pinfunction "2_2") (pintype "passive"))
      (node (ref "R41") (pin "1") (pinfunction "1_1") (pintype "passive"))
    )
    (net (code "49") (name "Net-(OSC_COARSE-S)") (class "Default")
      (node (ref "OSC_COARSE") (pin "P$2") (pinfunction "S_P$2") (pintype "passive"))
      (node (ref "R8") (pin "1") (pinfunction "1_1") (pintype "passive"))
    )
    (net (code "50") (name "Net-(OSC_FINE-S)") (class "Default")
      (node (ref "OSC_FINE") (pin "P$2") (pinfunction "S_P$2") (pintype "passive"))
      (node (ref "R3") (pin "1") (pinfunction "1_1") (pintype "passive"))
    )
    (net (code "51") (name "Net-(OSC_HI-E)") (class "Default")
      (node (ref "IC5") (pin "7") (pinfunction "7_7") (pintype "bidirectional"))
      (node (ref "OSC_HI") (pin "1") (pinfunction "E_1") (pintype "passive"))
    )
    (net (code "52") (name "Net-(OSC_HI-S)") (class "Default")
      (node (ref "OSC_HI") (pin "2") (pinfunction "S_2") (pintype "passive"))
      (node (ref "R18") (pin "1") (pinfunction "1_1") (pintype "passive"))
    )
    (net (code "53") (name "Net-(OSC_SCALE-A)") (class "Default")
      (node (ref "OSC_SCALE") (pin "3") (pinfunction "A_3") (pintype "passive"))
      (node (ref "R15") (pin "1") (pinfunction "1_1") (pintype "passive"))
    )
    (net (code "54") (name "Net-(PW-S)") (class "Default")
      (node (ref "PW") (pin "P$2") (pinfunction "S_P$2") (pintype "passive"))
      (node (ref "R26") (pin "1") (pinfunction "1_1") (pintype "passive"))
    )
    (net (code "55") (name "Net-(PWM-E)") (class "Default")
      (node (ref "PWM") (pin "P$1") (pinfunction "E_P$1") (pintype "passive"))
      (node (ref "PWM_IN") (pin "P3") (pinfunction "3_P3") (pintype "passive"))
    )
    (net (code "56") (name "Net-(PWM-S)") (class "Default")
      (node (ref "PWM") (pin "P$2") (pinfunction "S_P$2") (pintype "passive"))
      (node (ref "R36") (pin "1") (pinfunction "1_1") (pintype "passive"))
    )
    (net (code "57") (name "Net-(P_OUT-3)") (class "Default")
      (node (ref "P_OUT") (pin "P3") (pinfunction "3_P3") (pintype "passive"))
      (node (ref "R30") (pin "2") (pinfunction "2_2") (pintype "passive"))
    )
    (net (code "58") (name "Net-(SYNC_IN-3)") (class "Default")
      (node (ref "SYNC_IN") (pin "P3") (pinfunction "3_P3") (pintype "passive"))
      (node (ref "SYNC_SW") (pin "P$2") (pinfunction "P$2_P$2") (pintype "passive"))
    )
    (net (code "59") (name "Net-(S_OUT-3)") (class "Default")
      (node (ref "R41") (pin "2") (pinfunction "2_2") (pintype "passive"))
      (node (ref "S_OUT") (pin "P3") (pinfunction "3_P3") (pintype "passive"))
    )
    (net (code "60") (name "Net-(T_OUT-3)") (class "Default")
      (node (ref "R42") (pin "2") (pinfunction "2_2") (pintype "passive"))
      (node (ref "T_OUT") (pin "P3") (pinfunction "3_P3") (pintype "passive"))
    )
    (net (code "61") (name "Net-(V_OCT-3)") (class "Default")
      (node (ref "R14") (pin "1") (pinfunction "1_1") (pintype "passive"))
      (node (ref "V_OCT") (pin "P3") (pinfunction "3_P3") (pintype "passive"))
    )
    (net (code "62") (name "unconnected-(P_OUT-2-PadP2)") (class "Default")
      (node (ref "P_OUT") (pin "P2") (pinfunction "2_P2") (pintype "passive"))
    )
    (net (code "63") (name "unconnected-(S_OUT-2-PadP2)") (class "Default")
      (node (ref "S_OUT") (pin "P2") (pinfunction "2_P2") (pintype "passive"))
    )
    (net (code "64") (name "unconnected-(T_OUT-2-PadP2)") (class "Default")
      (node (ref "T_OUT") (pin "P2") (pinfunction "2_P2") (pintype "passive"))
    )
  )
)
